# Supply_LDOs.net
KiCad netlist of a schematic drawn in Altium Designer
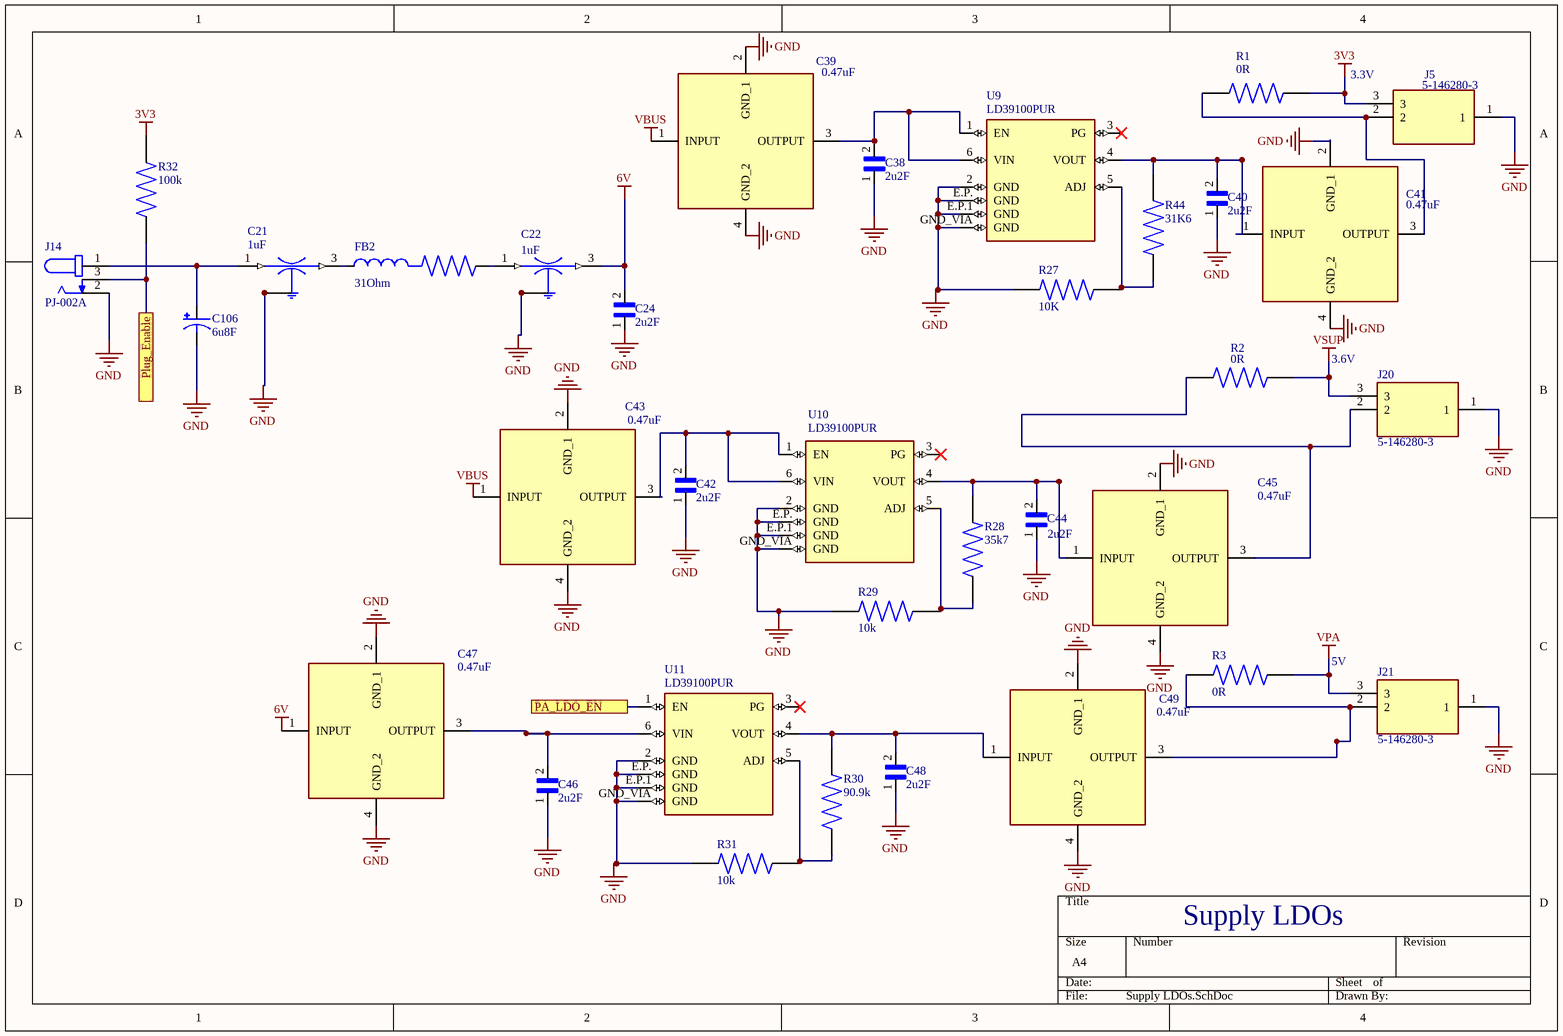
[diagram p0: Supply LDOs.SchDoc]

(export (version "E")
  (design (tool "Eeschema 10.0.6"))
  (components
    (comp (ref "C21")
      (value "1uF")
      (footprint "FIL_NFM21PC105B1A3D")
      (description "SMD Capacitor with Capacitance: 1.0uF Tol. 20%. Rated Voltage: 10Vdc")
      (fields (field (name "MF") "Murata") (field (name "MP") "NFM21PC105B1A3D"))
      (libsource (lib "NFM21PC105B1A3D") (part "NFM21PC105B1A3D"))
    )
    (comp (ref "C22")
      (value "1uF")
      (footprint "FIL_NFM21PC105B1A3D")
      (description "SMD Capacitor with Capacitance: 1.0uF Tol. 20%. Rated Voltage: 10Vdc")
      (fields (field (name "MF") "Murata") (field (name "MP") "NFM21PC105B1A3D"))
      (libsource (lib "NFM21PC105B1A3D") (part "NFM21PC105B1A3D"))
    )
    (comp (ref "C24")
      (value "2u2F")
      (footprint "CAPC0603X35N")
      (description "SMD Capacitor X5R(EIA) with Capacitance: 2.2uF Tol. 20%. Rated Voltage: 6.3Vdc")
      (fields (field (name "MP") "GRM033R60J225ME15D"))
      (libsource (lib "GRM033R60J225ME15D") (part "GRM033R60J225ME15D"))
    )
    (comp (ref "C38")
      (value "2u2F")
      (footprint "CAPC1005X55N")
      (description "CAPACITOR, MLCC, X5R, 2.2UF, 6.3V, 0402")
      (fields (field (name "MP") "GRM155R60J225ME95D"))
      (libsource (lib "GRM155R60J225ME95D") (part "GRM155R60J225ME95D"))
    )
    (comp (ref "C39")
      (value "0.47uF")
      (footprint "SamacSys:NFM18CC101R1C3D")
      (description "Capacitor")
      (fields
        (field (name "MANUFACTURER_PART_NUMBER") "NFM18PS474R0J3D")
        (field (name "MOUSER PART NUMBER") "81-NFM18PS474R0J3D")
      )
      (libsource (lib "*") (part "NFM18PS474R0J3D"))
    )
    (comp (ref "C40")
      (value "2u2F")
      (footprint "CAPC1005X55N")
      (description "CAPACITOR, MLCC, X5R, 2.2UF, 6.3V, 0402")
      (fields (field (name "MP") "GRM155R60J225ME95D"))
      (libsource (lib "") (part "GRM155R60J225ME95D_1"))
    )
    (comp (ref "C41")
      (value "0.47uF")
      (footprint "SamacSys:NFM18CC101R1C3D")
      (description "Capacitor")
      (fields
        (field (name "MANUFACTURER_PART_NUMBER") "NFM18PS474R0J3D")
        (field (name "MOUSER PART NUMBER") "81-NFM18PS474R0J3D")
      )
      (libsource (lib "*") (part "NFM18PS474R0J3D"))
    )
    (comp (ref "C42")
      (value "2u2F")
      (footprint "CAPC1005X55N")
      (description "CAPACITOR, MLCC, X5R, 2.2UF, 6.3V, 0402")
      (fields (field (name "MP") "GRM155R60J225ME95D"))
      (libsource (lib "GRM155R60J225ME95D") (part "GRM155R60J225ME95D"))
    )
    (comp (ref "C43")
      (value "0.47uF")
      (footprint "SamacSys:NFM18CC101R1C3D")
      (description "Capacitor")
      (fields
        (field (name "MANUFACTURER_PART_NUMBER") "NFM18PS474R0J3D")
        (field (name "MOUSER PART NUMBER") "81-NFM18PS474R0J3D")
      )
      (libsource (lib "*") (part "NFM18PS474R0J3D"))
    )
    (comp (ref "C44")
      (value "2u2F")
      (footprint "CAPC1005X55N")
      (description "CAPACITOR, MLCC, X5R, 2.2UF, 6.3V, 0402")
      (fields (field (name "MP") "GRM155R60J225ME95D"))
      (libsource (lib "") (part "GRM155R60J225ME95D_1"))
    )
    (comp (ref "C45")
      (value "0.47uF")
      (footprint "SamacSys:NFM18CC101R1C3D")
      (description "Capacitor")
      (fields
        (field (name "MANUFACTURER_PART_NUMBER") "NFM18PS474R0J3D")
        (field (name "MOUSER PART NUMBER") "81-NFM18PS474R0J3D")
      )
      (libsource (lib "*") (part "NFM18PS474R0J3D"))
    )
    (comp (ref "C46")
      (value "2u2F")
      (footprint "CAPC1005X55N")
      (description "CAPACITOR, MLCC, X5R, 2.2UF, 6.3V, 0402")
      (fields (field (name "MP") "GRM155R60J225ME95D"))
      (libsource (lib "GRM155R60J225ME95D") (part "GRM155R60J225ME95D"))
    )
    (comp (ref "C47")
      (value "0.47uF")
      (footprint "SamacSys:NFM18CC101R1C3D")
      (description "Capacitor")
      (fields
        (field (name "MANUFACTURER_PART_NUMBER") "NFM18PS474R0J3D")
        (field (name "MOUSER PART NUMBER") "81-NFM18PS474R0J3D")
      )
      (libsource (lib "*") (part "NFM18PS474R0J3D"))
    )
    (comp (ref "C48")
      (value "2u2F")
      (footprint "CAPC1005X55N")
      (description "CAPACITOR, MLCC, X5R, 2.2UF, 6.3V, 0402")
      (fields (field (name "MP") "GRM155R60J225ME95D"))
      (libsource (lib "GRM155R60J225ME95D") (part "GRM155R60J225ME95D"))
    )
    (comp (ref "C49")
      (value "0.47uF")
      (footprint "SamacSys:NFM18CC101R1C3D")
      (description "Capacitor")
      (fields
        (field (name "MANUFACTURER_PART_NUMBER") "NFM18PS474R0J3D")
        (field (name "MOUSER PART NUMBER") "81-NFM18PS474R0J3D")
      )
      (libsource (lib "*") (part "NFM18PS474R0J3D"))
    )
    (comp (ref "C106")
      (value "6u8F")
      (footprint "2917(POL)")
      (description "6.8 µF 16 V Aluminum - Polymer Capacitors 2917 (7343 Metric) 70mOhm 1000 Hrs @ 105°C")
      (fields (field (name "MF") "Murata") (field (name "MP") "ECASD41C685M070K00"))
      (libsource (lib "ECASD41C685M070K00") (part "ECASD41C685M070K00"))
    )
    (comp (ref "FB2")
      (value "31Ohm")
      (footprint "FIL_NFZ32BW310HN11L")
      (description "31 Ohms @ 1MHz 1 Ferrite Bead 2-SMD, Flat Lead 1.2A 186mOhm")
      (fields (field (name "MP") "NFZ32BW310HN11L") (field (name "MF") "Murata"))
      (libsource (lib "NFZ32BW310HN11L") (part "NFZ32BW310HN11L"))
    )
    (comp (ref "J5")
      (value "5-146280-3")
      (footprint "TE_5-146280-3")
      (description "Header; Conn; Interconnect System; PCB Plug; 3 Cont; Thru-Hole; Breakaway; Straight; 3A")
      (fields (field (name "MF") "TE Connectivity"))
      (libsource (lib "5-146280-3") (part "5-146280-3"))
    )
    (comp (ref "J14")
      (value "PJ-002A")
      (footprint "CUI_PJ-002A")
      (description "2.0 x 6.5 mm, 2.5 A, Horizontal, Through Hole, Dc Power Jack Connector")
      (fields (field (name "MF") "CUI Devices"))
      (libsource (lib "PJ-002A") (part "PJ-002A"))
    )
    (comp (ref "J20")
      (value "5-146280-3")
      (footprint "TE_5-146280-3")
      (description "Header; Conn; Interconnect System; PCB Plug; 3 Cont; Thru-Hole; Breakaway; Straight; 3A")
      (fields (field (name "MF") "TE Connectivity"))
      (libsource (lib "5-146280-3") (part "5-146280-3"))
    )
    (comp (ref "J21")
      (value "5-146280-3")
      (footprint "TE_5-146280-3")
      (description "Header; Conn; Interconnect System; PCB Plug; 3 Cont; Thru-Hole; Breakaway; Straight; 3A")
      (fields (field (name "MF") "TE Connectivity"))
      (libsource (lib "5-146280-3") (part "5-146280-3"))
    )
    (comp (ref "R1")
      (value "0R")
      (footprint "RESC1607X60N")
      (description "Thick film general purpose")
      (fields (field (name "MP") "RC0603JR-070RL"))
      (libsource (lib "RC0603JR-070RL") (part "RC0603JR-070RL"))
    )
    (comp (ref "R2")
      (value "0R")
      (footprint "RESC1607X60N")
      (description "Thick film general purpose")
      (fields (field (name "MP") "RC0603JR-070RL"))
      (libsource (lib "RC0603JR-070RL") (part "RC0603JR-070RL"))
    )
    (comp (ref "R3")
      (value "0R")
      (footprint "RESC1607X60N")
      (description "Thick film general purpose")
      (fields (field (name "MP") "RC0603JR-070RL"))
      (libsource (lib "RC0603JR-070RL") (part "RC0603JR-070RL"))
    )
    (comp (ref "R27")
      (value "10K")
      (footprint "RESC1005X40N")
      (description "10 kOhms Â±1% 0.063W, 1/16W Chip Resistor 0402 (1005 Metric) Moisture Resistant Thick Film")
      (fields (field (name "MF") "Yageo") (field (name "MP") "RC0402FR-0710KL"))
      (libsource (lib "RC0402FR-0710KL") (part "RC0402FR-0710KL"))
    )
    (comp (ref "R28")
      (value "35k7")
      (footprint "RESC1005X40N")
      (description "RES SMD 35.7K OHM 1% 1/16W 0402")
      (fields (field (name "MP") "RC0402FR-0735K7L"))
      (libsource (lib "RC0402FR-0735K7L") (part "RC0402FR-0735K7L"))
    )
    (comp (ref "R29")
      (value "10k")
      (footprint "RESC1005X40N")
      (description "10 kOhms Â±1% 0.063W, 1/16W Chip Resistor 0402 (1005 Metric) Moisture Resistant Thick Film")
      (fields (field (name "MF") "Yageo") (field (name "MP") "RC0402FR-0710KL"))
      (libsource (lib "RC0402FR-0710KL") (part "RC0402FR-0710KL"))
    )
    (comp (ref "R30")
      (value "90.9k")
      (footprint "RES_ERJ2RKF4222X")
      (fields (field (name "MP") "ERJ2RKF4222X"))
      (libsource (lib "ERJ2RKF4222X") (part "ERJ2RKF4222X"))
    )
    (comp (ref "R31")
      (value "10k")
      (footprint "RESC1005X40N")
      (description "10 kOhms Â±1% 0.063W, 1/16W Chip Resistor 0402 (1005 Metric) Moisture Resistant Thick Film")
      (fields (field (name "MF") "Yageo") (field (name "MP") "RC0402FR-0710KL"))
      (libsource (lib "RC0402FR-0710KL") (part "RC0402FR-0710KL"))
    )
    (comp (ref "R32")
      (value "100k")
      (footprint "RESC1005X40N")
      (description "Res Thick Film 0402 100K Ohm 1% 1/16W Â±100ppm/Â°C Molded SMD")
      (fields (field (name "MP") "RCG0402100KFKED"))
      (libsource (lib "RCG0402100KFKED") (part "RCG0402100KFKED"))
    )
    (comp (ref "R44")
      (value "31K6")
      (footprint "RESC1005X40N")
      (description "Thick film general purpose")
      (fields (field (name "MP") "RC0402FR-0731K6L"))
      (libsource (lib "RC0402FR-0731K6L") (part "RC0402FR-0731K6L"))
    )
    (comp (ref "U9")
      (value "LD39100PUR")
      (footprint "DFN6-3X3MM")
      (fields (field (name "MF") "STMicroelectronics"))
      (libsource (lib "LD39100PUR") (part "LD39100PUR"))
    )
    (comp (ref "U10")
      (value "LD39100PUR")
      (footprint "DFN6-3X3MM")
      (fields (field (name "MF") "STMicroelectronics"))
      (libsource (lib "LD39100PUR") (part "LD39100PUR"))
    )
    (comp (ref "U11")
      (value "LD39100PUR")
      (footprint "DFN6-3X3MM")
      (fields (field (name "MF") "STMicroelectronics"))
      (libsource (lib "LD39100PUR") (part "LD39100PUR"))
    )
  )
  (nets
    (net (code "1") (name "/PA_LDO_EN") (class "Default")
      (node (ref "U11") (pin "1") (pinfunction "EN_1") (pintype "bidirectional"))
    )
    (net (code "2") (name "/Plug_Enable") (class "Default")
      (node (ref "J14") (pin "3") (pinfunction "3_3") (pintype "passive"))
      (node (ref "R32") (pin "1") (pinfunction "1_1") (pintype "passive"))
    )
    (net (code "3") (name "3V3") (class "Default")
      (node (ref "J5") (pin "3") (pinfunction "3_3") (pintype "passive"))
      (node (ref "R1") (pin "2") (pinfunction "2_2") (pintype "passive"))
      (node (ref "R32") (pin "2") (pinfunction "2_2") (pintype "passive"))
    )
    (net (code "4") (name "6V") (class "Default")
      (node (ref "C22") (pin "3") (pinfunction "OUT_3") (pintype "output"))
      (node (ref "C24") (pin "2") (pinfunction "2_2") (pintype "passive"))
      (node (ref "C47") (pin "1") (pinfunction "INPUT_1") (pintype "passive"))
    )
    (net (code "5") (name "GND") (class "Default")
      (node (ref "C106") (pin "2") (pinfunction "NEG_2") (pintype "passive"))
      (node (ref "C21") (pin "2") (pinfunction "GND_2") (pintype "power_in"))
      (node (ref "C21") (pin "2_1") (pinfunction "GND_2_1") (pintype "power_in"))
      (node (ref "C21") (pin "2_2") (pinfunction "GND_2_2") (pintype "power_in"))
      (node (ref "C21") (pin "2_3") (pinfunction "GND_2_3") (pintype "power_in"))
      (node (ref "C21") (pin "2_4") (pinfunction "GND_2_4") (pintype "power_in"))
      (node (ref "C22") (pin "2") (pinfunction "GND_2") (pintype "power_in"))
      (node (ref "C22") (pin "2_1") (pinfunction "GND_2_1") (pintype "power_in"))
      (node (ref "C22") (pin "2_2") (pinfunction "GND_2_2") (pintype "power_in"))
      (node (ref "C22") (pin "2_3") (pinfunction "GND_2_3") (pintype "power_in"))
      (node (ref "C22") (pin "2_4") (pinfunction "GND_2_4") (pintype "power_in"))
      (node (ref "C24") (pin "1") (pinfunction "1_1") (pintype "passive"))
      (node (ref "C38") (pin "1") (pinfunction "1_1") (pintype "passive"))
      (node (ref "C39") (pin "2") (pinfunction "GND_1_2") (pintype "passive"))
      (node (ref "C39") (pin "4") (pinfunction "GND_2_4") (pintype "passive"))
      (node (ref "C40") (pin "1") (pinfunction "1_1") (pintype "passive"))
      (node (ref "C41") (pin "2") (pinfunction "GND_1_2") (pintype "passive"))
      (node (ref "C41") (pin "4") (pinfunction "GND_2_4") (pintype "passive"))
      (node (ref "C42") (pin "1") (pinfunction "1_1") (pintype "passive"))
      (node (ref "C43") (pin "2") (pinfunction "GND_1_2") (pintype "passive"))
      (node (ref "C43") (pin "4") (pinfunction "GND_2_4") (pintype "passive"))
      (node (ref "C44") (pin "1") (pinfunction "1_1") (pintype "passive"))
      (node (ref "C45") (pin "2") (pinfunction "GND_1_2") (pintype "passive"))
      (node (ref "C45") (pin "4") (pinfunction "GND_2_4") (pintype "passive"))
      (node (ref "C46") (pin "1") (pinfunction "1_1") (pintype "passive"))
      (node (ref "C47") (pin "2") (pinfunction "GND_1_2") (pintype "passive"))
      (node (ref "C47") (pin "4") (pinfunction "GND_2_4") (pintype "passive"))
      (node (ref "C48") (pin "1") (pinfunction "1_1") (pintype "passive"))
      (node (ref "C49") (pin "2") (pinfunction "GND_1_2") (pintype "passive"))
      (node (ref "C49") (pin "4") (pinfunction "GND_2_4") (pintype "passive"))
      (node (ref "J14") (pin "2") (pinfunction "2_2") (pintype "passive"))
      (node (ref "J20") (pin "1") (pinfunction "1_1") (pintype "passive"))
      (node (ref "J21") (pin "1") (pinfunction "1_1") (pintype "passive"))
      (node (ref "J5") (pin "1") (pinfunction "1_1") (pintype "passive"))
      (node (ref "R27") (pin "2") (pinfunction "2_2") (pintype "passive"))
      (node (ref "R29") (pin "2") (pinfunction "2_2") (pintype "passive"))
      (node (ref "R31") (pin "2") (pinfunction "2_2") (pintype "passive"))
      (node (ref "U10") (pin "2") (pinfunction "GND_2") (pintype "bidirectional"))
      (node (ref "U10") (pin "E.P.") (pinfunction "GND_E.P.") (pintype "bidirectional"))
      (node (ref "U10") (pin "E.P.1") (pinfunction "GND_E.P.1") (pintype "bidirectional"))
      (node (ref "U10") (pin "GND_VIA") (pinfunction "GND_GND_VIA") (pintype "bidirectional"))
      (node (ref "U11") (pin "2") (pinfunction "GND_2") (pintype "bidirectional"))
      (node (ref "U11") (pin "E.P.") (pinfunction "GND_E.P.") (pintype "bidirectional"))
      (node (ref "U11") (pin "E.P.1") (pinfunction "GND_E.P.1") (pintype "bidirectional"))
      (node (ref "U11") (pin "GND_VIA") (pinfunction "GND_GND_VIA") (pintype "bidirectional"))
      (node (ref "U9") (pin "2") (pinfunction "GND_2") (pintype "bidirectional"))
      (node (ref "U9") (pin "E.P.") (pinfunction "GND_E.P.") (pintype "bidirectional"))
      (node (ref "U9") (pin "E.P.1") (pinfunction "GND_E.P.1") (pintype "bidirectional"))
      (node (ref "U9") (pin "GND_VIA") (pinfunction "GND_GND_VIA") (pintype "bidirectional"))
    )
    (net (code "6") (name "Net-(C21-OUT)") (class "Default")
      (node (ref "C21") (pin "3") (pinfunction "OUT_3") (pintype "output"))
      (node (ref "FB2") (pin "1") (pinfunction "1_1") (pintype "passive"))
    )
    (net (code "7") (name "Net-(C22-IN)") (class "Default")
      (node (ref "C22") (pin "1") (pinfunction "IN_1") (pintype "input"))
      (node (ref "FB2") (pin "2") (pinfunction "2_2") (pintype "passive"))
    )
    (net (code "8") (name "Net-(C39-OUTPUT)") (class "Default")
      (node (ref "C38") (pin "2") (pinfunction "2_2") (pintype "passive"))
      (node (ref "C39") (pin "3") (pinfunction "OUTPUT_3") (pintype "passive"))
      (node (ref "U9") (pin "1") (pinfunction "EN_1") (pintype "bidirectional"))
      (node (ref "U9") (pin "6") (pinfunction "VIN_6") (pintype "bidirectional"))
    )
    (net (code "9") (name "Net-(C41-INPUT)") (class "Default")
      (node (ref "C40") (pin "2") (pinfunction "2_2") (pintype "passive"))
      (node (ref "C41") (pin "1") (pinfunction "INPUT_1") (pintype "passive"))
      (node (ref "R44") (pin "2") (pinfunction "2_2") (pintype "passive"))
      (node (ref "U9") (pin "4") (pinfunction "VOUT_4") (pintype "bidirectional"))
    )
    (net (code "10") (name "Net-(C41-OUTPUT)") (class "Default")
      (node (ref "C41") (pin "3") (pinfunction "OUTPUT_3") (pintype "passive"))
      (node (ref "J5") (pin "2") (pinfunction "2_2") (pintype "passive"))
      (node (ref "R1") (pin "1") (pinfunction "1_1") (pintype "passive"))
    )
    (net (code "11") (name "Net-(C43-OUTPUT)") (class "Default")
      (node (ref "C42") (pin "2") (pinfunction "2_2") (pintype "passive"))
      (node (ref "C43") (pin "3") (pinfunction "OUTPUT_3") (pintype "passive"))
      (node (ref "U10") (pin "1") (pinfunction "EN_1") (pintype "bidirectional"))
      (node (ref "U10") (pin "6") (pinfunction "VIN_6") (pintype "bidirectional"))
    )
    (net (code "12") (name "Net-(C45-INPUT)") (class "Default")
      (node (ref "C44") (pin "2") (pinfunction "2_2") (pintype "passive"))
      (node (ref "C45") (pin "1") (pinfunction "INPUT_1") (pintype "passive"))
      (node (ref "R28") (pin "2") (pinfunction "2_2") (pintype "passive"))
      (node (ref "U10") (pin "4") (pinfunction "VOUT_4") (pintype "bidirectional"))
    )
    (net (code "13") (name "Net-(C45-OUTPUT)") (class "Default")
      (node (ref "C45") (pin "3") (pinfunction "OUTPUT_3") (pintype "passive"))
      (node (ref "J20") (pin "2") (pinfunction "2_2") (pintype "passive"))
      (node (ref "R2") (pin "1") (pinfunction "1_1") (pintype "passive"))
    )
    (net (code "14") (name "Net-(C47-OUTPUT)") (class "Default")
      (node (ref "C46") (pin "2") (pinfunction "2_2") (pintype "passive"))
      (node (ref "C47") (pin "3") (pinfunction "OUTPUT_3") (pintype "passive"))
      (node (ref "U11") (pin "6") (pinfunction "VIN_6") (pintype "bidirectional"))
    )
    (net (code "15") (name "Net-(C49-INPUT)") (class "Default")
      (node (ref "C48") (pin "2") (pinfunction "2_2") (pintype "passive"))
      (node (ref "C49") (pin "1") (pinfunction "INPUT_1") (pintype "passive"))
      (node (ref "R30") (pin "2") (pinfunction "2_2") (pintype "passive"))
      (node (ref "U11") (pin "4") (pinfunction "VOUT_4") (pintype "bidirectional"))
    )
    (net (code "16") (name "Net-(C49-OUTPUT)") (class "Default")
      (node (ref "C49") (pin "3") (pinfunction "OUTPUT_3") (pintype "passive"))
      (node (ref "J21") (pin "2") (pinfunction "2_2") (pintype "passive"))
      (node (ref "R3") (pin "1") (pinfunction "1_1") (pintype "passive"))
    )
    (net (code "17") (name "Net-(C106-POS)") (class "Default")
      (node (ref "C106") (pin "1") (pinfunction "POS_1") (pintype "passive"))
      (node (ref "C21") (pin "1") (pinfunction "IN_1") (pintype "input"))
      (node (ref "J14") (pin "1") (pinfunction "1_1") (pintype "passive"))
    )
    (net (code "18") (name "Net-(U9-ADJ)") (class "Default")
      (node (ref "R27") (pin "1") (pinfunction "1_1") (pintype "passive"))
      (node (ref "R44") (pin "1") (pinfunction "1_1") (pintype "passive"))
      (node (ref "U9") (pin "5") (pinfunction "ADJ_5") (pintype "bidirectional"))
    )
    (net (code "19") (name "Net-(U10-ADJ)") (class "Default")
      (node (ref "R28") (pin "1") (pinfunction "1_1") (pintype "passive"))
      (node (ref "R29") (pin "1") (pinfunction "1_1") (pintype "passive"))
      (node (ref "U10") (pin "5") (pinfunction "ADJ_5") (pintype "bidirectional"))
    )
    (net (code "20") (name "Net-(U11-ADJ)") (class "Default")
      (node (ref "R30") (pin "1") (pinfunction "1_1") (pintype "passive"))
      (node (ref "R31") (pin "1") (pinfunction "1_1") (pintype "passive"))
      (node (ref "U11") (pin "5") (pinfunction "ADJ_5") (pintype "bidirectional"))
    )
    (net (code "21") (name "VBUS") (class "Default")
      (node (ref "C39") (pin "1") (pinfunction "INPUT_1") (pintype "passive"))
      (node (ref "C43") (pin "1") (pinfunction "INPUT_1") (pintype "passive"))
    )
    (net (code "22") (name "VPA") (class "Default")
      (node (ref "J21") (pin "3") (pinfunction "3_3") (pintype "passive"))
      (node (ref "R3") (pin "2") (pinfunction "2_2") (pintype "passive"))
    )
    (net (code "23") (name "VSUP") (class "Default")
      (node (ref "J20") (pin "3") (pinfunction "3_3") (pintype "passive"))
      (node (ref "R2") (pin "2") (pinfunction "2_2") (pintype "passive"))
    )
    (net (code "24") (name "unconnected-(U9-PG-Pad3)") (class "Default")
      (node (ref "U9") (pin "3") (pinfunction "PG_3") (pintype "bidirectional+no_connect"))
    )
    (net (code "25") (name "unconnected-(U10-PG-Pad3)") (class "Default")
      (node (ref "U10") (pin "3") (pinfunction "PG_3") (pintype "bidirectional+no_connect"))
    )
    (net (code "26") (name "unconnected-(U11-PG-Pad3)") (class "Default")
      (node (ref "U11") (pin "3") (pinfunction "PG_3") (pintype "bidirectional+no_connect"))
    )
  )
)
